# hammer-of-blues.net
KiCad netlist of a schematic drawn in EAGLE
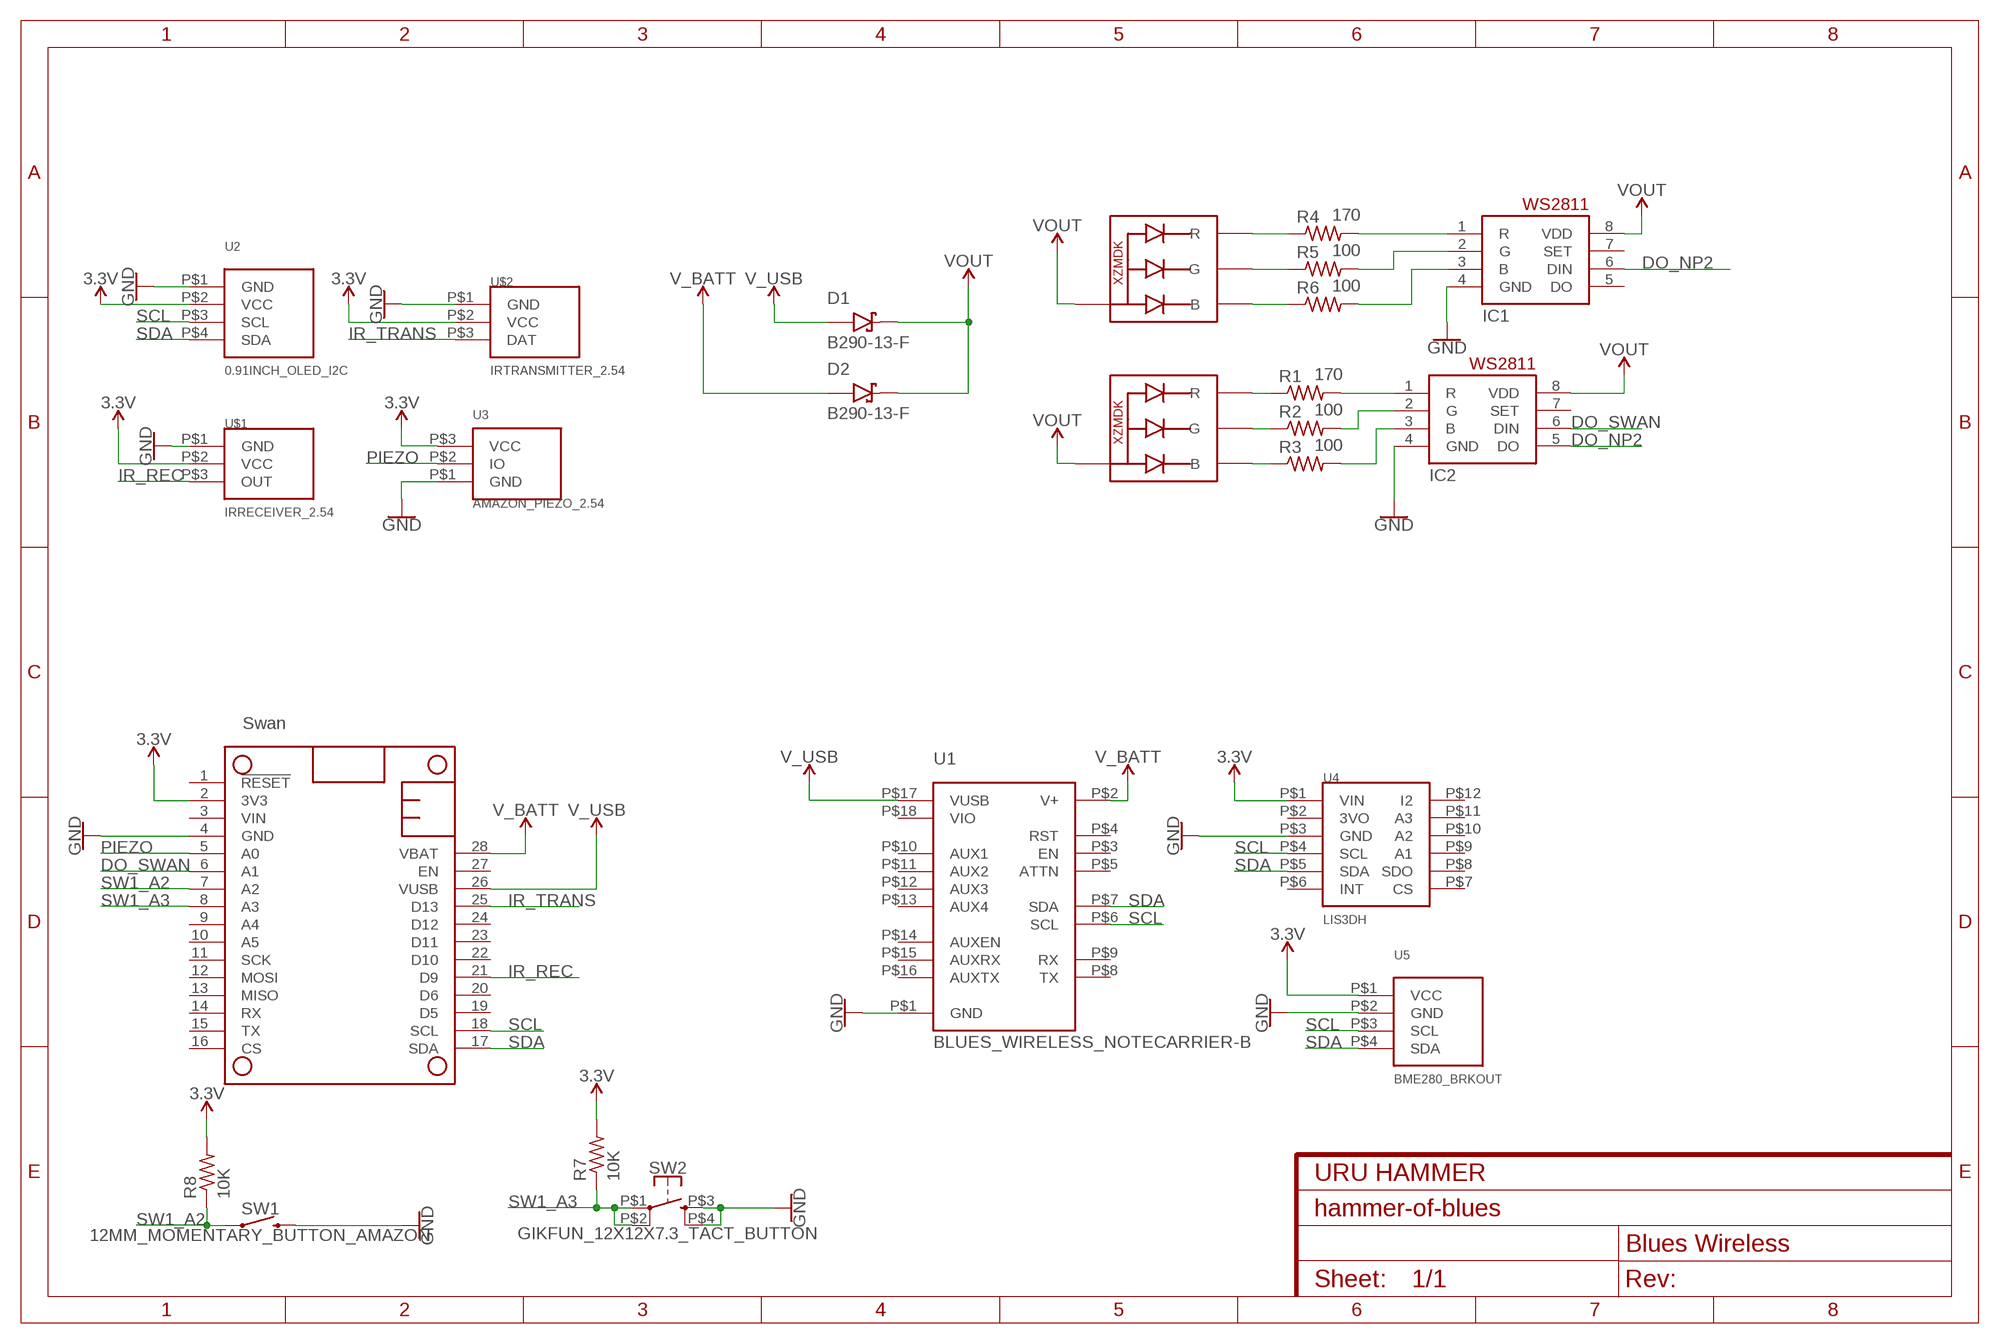
[diagram p0: schematic, sheet 1]

(export (version "E")
  (design (tool "Eeschema 10.0.6"))
  (components
    (comp (ref "D1")
      (value "B290-13-F")
      (footprint "eagle-import:DIOM4336X250N")
      (fields (field (name "MF") "Diodes Inc."))
      (libsource (lib "eagle-import") (part "B290-13-F"))
    )
    (comp (ref "D2")
      (value "B290-13-F")
      (footprint "eagle-import:DIOM4336X250N")
      (fields (field (name "MF") "Diodes Inc."))
      (libsource (lib "eagle-import") (part "B290-13-F"))
    )
    (comp (ref "IC1")
      (value "WS2811-SOP8")
      (footprint "eagle-import:SO08-SKINNYPADS")
      (libsource (lib "eagle-import") (part "WS2811-SOP8"))
    )
    (comp (ref "IC2")
      (value "WS2811-SOP8")
      (footprint "eagle-import:SO08-SKINNYPADS")
      (libsource (lib "eagle-import") (part "WS2811-SOP8"))
    )
    (comp (ref "LED1")
      (value "XZMDKCBDDG45S-9")
      (footprint "eagle-import:XZMDKCBDDG45S-9")
      (libsource (lib "eagle-import") (part "XZMDKCBDDG45S-9"))
    )
    (comp (ref "LED2")
      (value "XZMDKCBDDG45S-9")
      (footprint "eagle-import:XZMDKCBDDG45S-9")
      (libsource (lib "eagle-import") (part "XZMDKCBDDG45S-9"))
    )
    (comp (ref "MOD1")
      (value "BLUES_WIRELESS_SWAN_2.54BLUES_WIRELESS_SWAN_2.54_HEADERS")
      (footprint "eagle-import:BLUES_WIRELESS_SWAN_2.54_HEADERS")
      (libsource (lib "eagle-import") (part "BLUES_WIRELESS_SWAN_2.54BLUES_WIRELESS_SWAN_2.54_HEADERS"))
    )
    (comp (ref "R1")
      (value "170")
      (footprint "eagle-import:R0805")
      (libsource (lib "eagle-import") (part "R-US_R0805"))
    )
    (comp (ref "R2")
      (value "100")
      (footprint "eagle-import:R0805")
      (libsource (lib "eagle-import") (part "R-US_R0805"))
    )
    (comp (ref "R3")
      (value "100")
      (footprint "eagle-import:R0805")
      (libsource (lib "eagle-import") (part "R-US_R0805"))
    )
    (comp (ref "R4")
      (value "170")
      (footprint "eagle-import:R0805")
      (libsource (lib "eagle-import") (part "R-US_R0805"))
    )
    (comp (ref "R5")
      (value "100")
      (footprint "eagle-import:R0805")
      (libsource (lib "eagle-import") (part "R-US_R0805"))
    )
    (comp (ref "R6")
      (value "100")
      (footprint "eagle-import:R0805")
      (libsource (lib "eagle-import") (part "R-US_R0805"))
    )
    (comp (ref "R7")
      (value "10K")
      (footprint "eagle-import:R0805")
      (libsource (lib "eagle-import") (part "R-US_R0805"))
    )
    (comp (ref "R8")
      (value "10K")
      (footprint "eagle-import:R0805")
      (libsource (lib "eagle-import") (part "R-US_R0805"))
    )
    (comp (ref "SW1")
      (value "12MM_MOMENTARY_BUTTON_AMAZON")
      (footprint "eagle-import:12MM_MOMENTARY_BUTTON_AMAZON")
      (libsource (lib "eagle-import") (part "12MM_MOMENTARY_BUTTON_AMAZON"))
    )
    (comp (ref "SW2")
      (value "GIKFUN_12X12X7.3_TACT_BUTTON")
      (footprint "eagle-import:GIKFUN_12X12X7.3_TACT_BUTTON")
      (libsource (lib "eagle-import") (part "GIKFUN_12X12X7.3_TACT_BUTTON"))
    )
    (comp (ref "U$1")
      (value "IRRECEIVER_2.54")
      (footprint "eagle-import:IRRECEIVER_2.54")
      (libsource (lib "eagle-import") (part "IRRECEIVER_2.54"))
    )
    (comp (ref "U$2")
      (value "IRTRANSMITTER_2.54")
      (footprint "eagle-import:IRTRANSMITTER_2.54")
      (libsource (lib "eagle-import") (part "IRTRANSMITTER_2.54"))
    )
    (comp (ref "U1")
      (value "BLUES_WIRELESS_NOTECARRIER-B")
      (footprint "eagle-import:BLUES_WIRELESS_NOTECARRIER-B")
      (libsource (lib "eagle-import") (part "BLUES_WIRELESS_NOTECARRIER-B"))
    )
    (comp (ref "U2")
      (value "0.91INCH_OLED_I2C")
      (footprint "eagle-import:0.91INCH_OLED_I2C")
      (libsource (lib "eagle-import") (part "0.91INCH_OLED_I2C"))
    )
    (comp (ref "U3")
      (value "AMAZON_PIEZO_2.54")
      (footprint "eagle-import:AMAZON_PIEZO_2.54")
      (libsource (lib "eagle-import") (part "AMAZON_PIEZO_2.54"))
    )
    (comp (ref "U4")
      (value "LIS3DH")
      (footprint "eagle-import:LIS3DH_QWIIC")
      (libsource (lib "eagle-import") (part "LIS3DH"))
    )
    (comp (ref "U5")
      (value "BME280_BRKOUT")
      (footprint "eagle-import:BME280_BRKOUT")
      (libsource (lib "eagle-import") (part "BME280_BRKOUT"))
    )
  )
  (nets
    (net (code "1") (name "/DO_NP2") (class "Default")
      (node (ref "IC1") (pin "6") (pinfunction "DIN_6") (pintype "input"))
      (node (ref "IC2") (pin "5") (pinfunction "DO_5") (pintype "output"))
    )
    (net (code "2") (name "/DO_SWAN") (class "Default")
      (node (ref "IC2") (pin "6") (pinfunction "DIN_6") (pintype "input"))
      (node (ref "MOD1") (pin "6") (pinfunction "A1_6") (pintype "bidirectional"))
    )
    (net (code "3") (name "/IR_REC") (class "Default")
      (node (ref "MOD1") (pin "21") (pinfunction "D9_21") (pintype "bidirectional"))
      (node (ref "U$1") (pin "P$3") (pinfunction "OUT_P$3") (pintype "bidirectional"))
    )
    (net (code "4") (name "/IR_TRANS") (class "Default")
      (node (ref "MOD1") (pin "25") (pinfunction "D13_25") (pintype "bidirectional"))
      (node (ref "U$2") (pin "P$3") (pinfunction "DAT_P$3") (pintype "bidirectional"))
    )
    (net (code "5") (name "/PIEZO") (class "Default")
      (node (ref "MOD1") (pin "5") (pinfunction "A0_5") (pintype "bidirectional"))
      (node (ref "U3") (pin "P$2") (pinfunction "IO_P$2") (pintype "bidirectional"))
    )
    (net (code "6") (name "/SCL") (class "Default")
      (node (ref "MOD1") (pin "18") (pinfunction "SCL_18") (pintype "bidirectional"))
      (node (ref "U1") (pin "P$6") (pinfunction "SCL_P$6") (pintype "bidirectional"))
      (node (ref "U2") (pin "P$3") (pinfunction "SCL_P$3") (pintype "bidirectional"))
      (node (ref "U4") (pin "P$4") (pinfunction "SCL_P$4") (pintype "bidirectional"))
      (node (ref "U5") (pin "P$3") (pinfunction "SCL_P$3") (pintype "bidirectional"))
    )
    (net (code "7") (name "/SDA") (class "Default")
      (node (ref "MOD1") (pin "17") (pinfunction "SDA_17") (pintype "bidirectional"))
      (node (ref "U1") (pin "P$7") (pinfunction "SDA_P$7") (pintype "bidirectional"))
      (node (ref "U2") (pin "P$4") (pinfunction "SDA_P$4") (pintype "bidirectional"))
      (node (ref "U4") (pin "P$5") (pinfunction "SDA_P$5") (pintype "bidirectional"))
      (node (ref "U5") (pin "P$4") (pinfunction "SDA_P$4") (pintype "bidirectional"))
    )
    (net (code "8") (name "/SW1_A2") (class "Default")
      (node (ref "MOD1") (pin "7") (pinfunction "A2_7") (pintype "bidirectional"))
      (node (ref "R8") (pin "1") (pinfunction "1_1") (pintype "passive"))
      (node (ref "SW1") (pin "P$1") (pinfunction "1_P$1") (pintype "passive"))
    )
    (net (code "9") (name "/SW1_A3") (class "Default")
      (node (ref "MOD1") (pin "8") (pinfunction "A3_8") (pintype "bidirectional"))
      (node (ref "R7") (pin "1") (pinfunction "1_1") (pintype "passive"))
      (node (ref "SW2") (pin "P$1") (pinfunction "1_P$1") (pintype "passive"))
      (node (ref "SW2") (pin "P$2") (pinfunction "2_P$2") (pintype "passive"))
    )
    (net (code "10") (name "/VIN") (class "Default")
      (node (ref "MOD1") (pin "3") (pinfunction "VIN_3") (pintype "power_in"))
    )
    (net (code "11") (name "3.3V") (class "Default")
      (node (ref "MOD1") (pin "2") (pinfunction "3V3_2") (pintype "power_in"))
      (node (ref "R7") (pin "2") (pinfunction "2_2") (pintype "passive"))
      (node (ref "R8") (pin "2") (pinfunction "2_2") (pintype "passive"))
      (node (ref "U$1") (pin "P$2") (pinfunction "VCC_P$2") (pintype "bidirectional"))
      (node (ref "U$2") (pin "P$2") (pinfunction "VCC_P$2") (pintype "bidirectional"))
      (node (ref "U2") (pin "P$2") (pinfunction "VCC_P$2") (pintype "bidirectional"))
      (node (ref "U3") (pin "P$3") (pinfunction "VCC_P$3") (pintype "bidirectional"))
      (node (ref "U4") (pin "P$1") (pinfunction "VIN_P$1") (pintype "bidirectional"))
      (node (ref "U5") (pin "P$1") (pinfunction "VCC_P$1") (pintype "bidirectional"))
    )
    (net (code "12") (name "GND") (class "Default")
      (node (ref "IC1") (pin "4") (pinfunction "GND_4") (pintype "power_in"))
      (node (ref "IC2") (pin "4") (pinfunction "GND_4") (pintype "power_in"))
      (node (ref "MOD1") (pin "4") (pinfunction "GND_4") (pintype "power_in"))
      (node (ref "SW1") (pin "P$2") (pinfunction "2_P$2") (pintype "passive"))
      (node (ref "SW2") (pin "P$3") (pinfunction "3_P$3") (pintype "passive"))
      (node (ref "SW2") (pin "P$4") (pinfunction "4_P$4") (pintype "passive"))
      (node (ref "U$1") (pin "P$1") (pinfunction "GND_P$1") (pintype "bidirectional"))
      (node (ref "U$2") (pin "P$1") (pinfunction "GND_P$1") (pintype "bidirectional"))
      (node (ref "U1") (pin "P$1") (pinfunction "GND_P$1") (pintype "bidirectional"))
      (node (ref "U2") (pin "P$1") (pinfunction "GND_P$1") (pintype "bidirectional"))
      (node (ref "U3") (pin "P$1") (pinfunction "GND_P$1") (pintype "bidirectional"))
      (node (ref "U4") (pin "P$3") (pinfunction "GND_P$3") (pintype "bidirectional"))
      (node (ref "U5") (pin "P$2") (pinfunction "GND_P$2") (pintype "bidirectional"))
    )
    (net (code "13") (name "Net-(IC1-B)") (class "Default")
      (node (ref "IC1") (pin "3") (pinfunction "B_3") (pintype "open_collector"))
      (node (ref "R6") (pin "2") (pinfunction "2_2") (pintype "passive"))
    )
    (net (code "14") (name "Net-(IC1-G)") (class "Default")
      (node (ref "IC1") (pin "2") (pinfunction "G_2") (pintype "open_collector"))
      (node (ref "R5") (pin "2") (pinfunction "2_2") (pintype "passive"))
    )
    (net (code "15") (name "Net-(IC1-R)") (class "Default")
      (node (ref "IC1") (pin "1") (pinfunction "R_1") (pintype "open_collector"))
      (node (ref "R4") (pin "2") (pinfunction "2_2") (pintype "passive"))
    )
    (net (code "16") (name "Net-(IC2-B)") (class "Default")
      (node (ref "IC2") (pin "3") (pinfunction "B_3") (pintype "open_collector"))
      (node (ref "R3") (pin "2") (pinfunction "2_2") (pintype "passive"))
    )
    (net (code "17") (name "Net-(IC2-G)") (class "Default")
      (node (ref "IC2") (pin "2") (pinfunction "G_2") (pintype "open_collector"))
      (node (ref "R2") (pin "2") (pinfunction "2_2") (pintype "passive"))
    )
    (net (code "18") (name "Net-(IC2-R)") (class "Default")
      (node (ref "IC2") (pin "1") (pinfunction "R_1") (pintype "open_collector"))
      (node (ref "R1") (pin "2") (pinfunction "2_2") (pintype "passive"))
    )
    (net (code "19") (name "Net-(LED1-B)") (class "Default")
      (node (ref "LED1") (pin "P$3") (pinfunction "B_P$3") (pintype "passive"))
      (node (ref "R3") (pin "1") (pinfunction "1_1") (pintype "passive"))
    )
    (net (code "20") (name "Net-(LED1-G)") (class "Default")
      (node (ref "LED1") (pin "P$4") (pinfunction "G_P$4") (pintype "passive"))
      (node (ref "R2") (pin "1") (pinfunction "1_1") (pintype "passive"))
    )
    (net (code "21") (name "Net-(LED1-R)") (class "Default")
      (node (ref "LED1") (pin "P$1") (pinfunction "R_P$1") (pintype "passive"))
      (node (ref "R1") (pin "1") (pinfunction "1_1") (pintype "passive"))
    )
    (net (code "22") (name "Net-(LED2-B)") (class "Default")
      (node (ref "LED2") (pin "P$3") (pinfunction "B_P$3") (pintype "passive"))
      (node (ref "R6") (pin "1") (pinfunction "1_1") (pintype "passive"))
    )
    (net (code "23") (name "Net-(LED2-G)") (class "Default")
      (node (ref "LED2") (pin "P$4") (pinfunction "G_P$4") (pintype "passive"))
      (node (ref "R5") (pin "1") (pinfunction "1_1") (pintype "passive"))
    )
    (net (code "24") (name "Net-(LED2-R)") (class "Default")
      (node (ref "LED2") (pin "P$1") (pinfunction "R_P$1") (pintype "passive"))
      (node (ref "R4") (pin "1") (pinfunction "1_1") (pintype "passive"))
    )
    (net (code "25") (name "VOUT") (class "Default")
      (node (ref "D1") (pin "C") (pinfunction "K_C") (pintype "passive"))
      (node (ref "D2") (pin "C") (pinfunction "K_C") (pintype "passive"))
      (node (ref "IC1") (pin "8") (pinfunction "VDD_8") (pintype "power_in"))
      (node (ref "IC2") (pin "8") (pinfunction "VDD_8") (pintype "power_in"))
      (node (ref "LED1") (pin "P$2") (pinfunction "VDD_P$2") (pintype "passive"))
      (node (ref "LED2") (pin "P$2") (pinfunction "VDD_P$2") (pintype "passive"))
    )
    (net (code "26") (name "V_BATT") (class "Default")
      (node (ref "D2") (pin "A") (pinfunction "A_A") (pintype "passive"))
      (node (ref "MOD1") (pin "28") (pinfunction "VBAT_28") (pintype "power_in"))
      (node (ref "U1") (pin "P$2") (pinfunction "V+_P$2") (pintype "bidirectional"))
    )
    (net (code "27") (name "V_USB") (class "Default")
      (node (ref "D1") (pin "A") (pinfunction "A_A") (pintype "passive"))
      (node (ref "MOD1") (pin "26") (pinfunction "VUSB_26") (pintype "power_in"))
      (node (ref "U1") (pin "P$17") (pinfunction "VUSB_P$17") (pintype "bidirectional"))
    )
    (net (code "28") (name "unconnected-(IC1-DO-Pad5)") (class "Default")
      (node (ref "IC1") (pin "5") (pinfunction "DO_5") (pintype "output"))
    )
    (net (code "29") (name "unconnected-(IC1-SET-Pad7)") (class "Default")
      (node (ref "IC1") (pin "7") (pinfunction "SET_7") (pintype "input"))
    )
    (net (code "30") (name "unconnected-(IC2-SET-Pad7)") (class "Default")
      (node (ref "IC2") (pin "7") (pinfunction "SET_7") (pintype "input"))
    )
    (net (code "31") (name "unconnected-(MOD1-A4-Pad9)") (class "Default")
      (node (ref "MOD1") (pin "9") (pinfunction "A4_9") (pintype "bidirectional"))
    )
    (net (code "32") (name "unconnected-(MOD1-A5-Pad10)") (class "Default")
      (node (ref "MOD1") (pin "10") (pinfunction "A5_10") (pintype "bidirectional"))
    )
    (net (code "33") (name "unconnected-(MOD1-CS-Pad16)") (class "Default")
      (node (ref "MOD1") (pin "16") (pinfunction "CS_16") (pintype "passive"))
    )
    (net (code "34") (name "unconnected-(MOD1-D5-Pad19)") (class "Default")
      (node (ref "MOD1") (pin "19") (pinfunction "D5_19") (pintype "bidirectional"))
    )
    (net (code "35") (name "unconnected-(MOD1-D6-Pad20)") (class "Default")
      (node (ref "MOD1") (pin "20") (pinfunction "D6_20") (pintype "bidirectional"))
    )
    (net (code "36") (name "unconnected-(MOD1-D10-Pad22)") (class "Default")
      (node (ref "MOD1") (pin "22") (pinfunction "D10_22") (pintype "bidirectional"))
    )
    (net (code "37") (name "unconnected-(MOD1-D11-Pad23)") (class "Default")
      (node (ref "MOD1") (pin "23") (pinfunction "D11_23") (pintype "bidirectional"))
    )
    (net (code "38") (name "unconnected-(MOD1-D12-Pad24)") (class "Default")
      (node (ref "MOD1") (pin "24") (pinfunction "D12_24") (pintype "bidirectional"))
    )
    (net (code "39") (name "unconnected-(MOD1-EN-Pad27)") (class "Default")
      (node (ref "MOD1") (pin "27") (pinfunction "EN_27") (pintype "passive"))
    )
    (net (code "40") (name "unconnected-(MOD1-MISO-Pad13)") (class "Default")
      (node (ref "MOD1") (pin "13") (pinfunction "MISO_13") (pintype "bidirectional"))
    )
    (net (code "41") (name "unconnected-(MOD1-MOSI-Pad12)") (class "Default")
      (node (ref "MOD1") (pin "12") (pinfunction "MOSI_12") (pintype "bidirectional"))
    )
    (net (code "42") (name "unconnected-(MOD1-RX-Pad14)") (class "Default")
      (node (ref "MOD1") (pin "14") (pinfunction "RX_14") (pintype "bidirectional"))
    )
    (net (code "43") (name "unconnected-(MOD1-SCK-Pad11)") (class "Default")
      (node (ref "MOD1") (pin "11") (pinfunction "SCK_11") (pintype "bidirectional"))
    )
    (net (code "44") (name "unconnected-(MOD1-TX-Pad15)") (class "Default")
      (node (ref "MOD1") (pin "15") (pinfunction "TX_15") (pintype "bidirectional"))
    )
    (net (code "45") (name "unconnected-(MOD1-~{RESET}-Pad1)") (class "Default")
      (node (ref "MOD1") (pin "1") (pinfunction "~{RESET}_1") (pintype "input"))
    )
    (net (code "46") (name "unconnected-(U1-ATTN-PadP$5)") (class "Default")
      (node (ref "U1") (pin "P$5") (pinfunction "ATTN_P$5") (pintype "bidirectional"))
    )
    (net (code "47") (name "unconnected-(U1-AUX1-PadP$10)") (class "Default")
      (node (ref "U1") (pin "P$10") (pinfunction "AUX1_P$10") (pintype "bidirectional"))
    )
    (net (code "48") (name "unconnected-(U1-AUX2-PadP$11)") (class "Default")
      (node (ref "U1") (pin "P$11") (pinfunction "AUX2_P$11") (pintype "bidirectional"))
    )
    (net (code "49") (name "unconnected-(U1-AUX3-PadP$12)") (class "Default")
      (node (ref "U1") (pin "P$12") (pinfunction "AUX3_P$12") (pintype "bidirectional"))
    )
    (net (code "50") (name "unconnected-(U1-AUX4-PadP$13)") (class "Default")
      (node (ref "U1") (pin "P$13") (pinfunction "AUX4_P$13") (pintype "bidirectional"))
    )
    (net (code "51") (name "unconnected-(U1-AUXEN-PadP$14)") (class "Default")
      (node (ref "U1") (pin "P$14") (pinfunction "AUXEN_P$14") (pintype "bidirectional"))
    )
    (net (code "52") (name "unconnected-(U1-AUXRX-PadP$15)") (class "Default")
      (node (ref "U1") (pin "P$15") (pinfunction "AUXRX_P$15") (pintype "bidirectional"))
    )
    (net (code "53") (name "unconnected-(U1-AUXTX-PadP$16)") (class "Default")
      (node (ref "U1") (pin "P$16") (pinfunction "AUXTX_P$16") (pintype "bidirectional"))
    )
    (net (code "54") (name "unconnected-(U1-EN-PadP$3)") (class "Default")
      (node (ref "U1") (pin "P$3") (pinfunction "EN_P$3") (pintype "bidirectional"))
    )
    (net (code "55") (name "unconnected-(U1-RST-PadP$4)") (class "Default")
      (node (ref "U1") (pin "P$4") (pinfunction "RST_P$4") (pintype "bidirectional"))
    )
    (net (code "56") (name "unconnected-(U1-RX-PadP$9)") (class "Default")
      (node (ref "U1") (pin "P$9") (pinfunction "RX_P$9") (pintype "bidirectional"))
    )
    (net (code "57") (name "unconnected-(U1-TX-PadP$8)") (class "Default")
      (node (ref "U1") (pin "P$8") (pinfunction "TX_P$8") (pintype "bidirectional"))
    )
    (net (code "58") (name "unconnected-(U1-VIO-PadP$18)") (class "Default")
      (node (ref "U1") (pin "P$18") (pinfunction "VIO_P$18") (pintype "bidirectional"))
    )
    (net (code "59") (name "unconnected-(U4-3VO-PadP$2)") (class "Default")
      (node (ref "U4") (pin "P$2") (pinfunction "3VO_P$2") (pintype "bidirectional"))
    )
    (net (code "60") (name "unconnected-(U4-A1-PadP$9)") (class "Default")
      (node (ref "U4") (pin "P$9") (pinfunction "A1_P$9") (pintype "bidirectional"))
    )
    (net (code "61") (name "unconnected-(U4-A2-PadP$10)") (class "Default")
      (node (ref "U4") (pin "P$10") (pinfunction "A2_P$10") (pintype "bidirectional"))
    )
    (net (code "62") (name "unconnected-(U4-A3-PadP$11)") (class "Default")
      (node (ref "U4") (pin "P$11") (pinfunction "A3_P$11") (pintype "bidirectional"))
    )
    (net (code "63") (name "unconnected-(U4-CS-PadP$7)") (class "Default")
      (node (ref "U4") (pin "P$7") (pinfunction "CS_P$7") (pintype "bidirectional"))
    )
    (net (code "64") (name "unconnected-(U4-I2-PadP$12)") (class "Default")
      (node (ref "U4") (pin "P$12") (pinfunction "I2_P$12") (pintype "bidirectional"))
    )
    (net (code "65") (name "unconnected-(U4-INT-PadP$6)") (class "Default")
      (node (ref "U4") (pin "P$6") (pinfunction "INT_P$6") (pintype "bidirectional"))
    )
    (net (code "66") (name "unconnected-(U4-SDO-PadP$8)") (class "Default")
      (node (ref "U4") (pin "P$8") (pinfunction "SDO_P$8") (pintype "bidirectional"))
    )
  )
)
